# Power_Supply.net
KiCad netlist of a schematic drawn in EAGLE
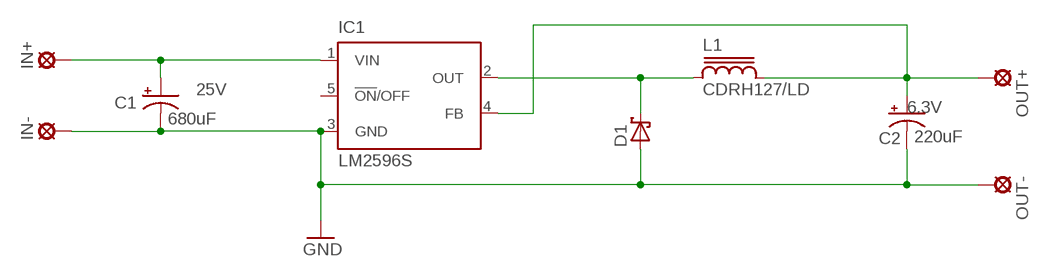
[diagram p0: schematic, sheet 1]

(export (version "E")
  (design (tool "Eeschema 10.0.6"))
  (components
    (comp (ref "C1")
      (value "680uF")
      (footprint "eagle-import:E5-10,5")
      (fields (field (name "VOLTAGE") "25V"))
      (libsource (lib "eagle-import") (part "CPOL-USE5-10.5"))
    )
    (comp (ref "C2")
      (value "220uF")
      (footprint "eagle-import:UD-6,3X5,8_NICHICON")
      (fields (field (name "VOLTAGE") "6.3V"))
      (libsource (lib "eagle-import") (part "CPOL-USUD-6,3X5,8"))
    )
    (comp (ref "D1")
      (value "SCHOTTKY-DIODESMD")
      (footprint "eagle-import:SMB")
      (libsource (lib "eagle-import") (part "SCHOTTKY-DIODESMD"))
    )
    (comp (ref "IC1")
      (value "LM2596S")
      (footprint "eagle-import:TO263-5")
      (fields (field (name "MF") "NATIONAL SEMICONDUCTOR") (field (name "MPN") "LM2596S-ADJ/NOPB"))
      (libsource (lib "eagle-import") (part "LM2596S"))
    )
    (comp (ref "IN+")
      (value "LSP13")
      (footprint "eagle-import:LSP13")
      (libsource (lib "eagle-import") (part "LSP13"))
    )
    (comp (ref "IN-")
      (value "LSP13")
      (footprint "eagle-import:LSP13")
      (libsource (lib "eagle-import") (part "LSP13"))
    )
    (comp (ref "L1")
      (value "CDRH127/LD")
      (footprint "eagle-import:CDRH127_LD")
      (libsource (lib "eagle-import") (part "CDRH127/LD"))
    )
    (comp (ref "OUT+")
      (value "LSP13")
      (footprint "eagle-import:LSP13")
      (libsource (lib "eagle-import") (part "LSP13"))
    )
    (comp (ref "OUT-")
      (value "LSP13")
      (footprint "eagle-import:LSP13")
      (libsource (lib "eagle-import") (part "LSP13"))
    )
  )
  (nets
    (net (code "1") (name "GND") (class "Default")
      (node (ref "C1") (pin "-") (pinfunction "-_-") (pintype "passive"))
      (node (ref "C2") (pin "-") (pinfunction "-_-") (pintype "passive"))
      (node (ref "D1") (pin "A") (pinfunction "A_A") (pintype "passive"))
      (node (ref "IC1") (pin "3") (pinfunction "GND_3") (pintype "power_in"))
      (node (ref "IN-") (pin "MP") (pinfunction "MP_MP") (pintype "passive"))
      (node (ref "OUT-") (pin "MP") (pinfunction "MP_MP") (pintype "passive"))
    )
    (net (code "2") (name "Net-(IC1-FB)") (class "Default")
      (node (ref "C2") (pin "+") (pinfunction "+_+") (pintype "passive"))
      (node (ref "IC1") (pin "4") (pinfunction "FB_4") (pintype "input"))
      (node (ref "L1") (pin "2") (pinfunction "2_2") (pintype "passive"))
      (node (ref "OUT+") (pin "MP") (pinfunction "MP_MP") (pintype "passive"))
    )
    (net (code "3") (name "Net-(IC1-OUT)") (class "Default")
      (node (ref "D1") (pin "C") (pinfunction "C_C") (pintype "passive"))
      (node (ref "IC1") (pin "2") (pinfunction "OUT_2") (pintype "output"))
      (node (ref "L1") (pin "1") (pinfunction "1_1") (pintype "passive"))
    )
    (net (code "4") (name "Net-(IC1-VIN)") (class "Default")
      (node (ref "C1") (pin "+") (pinfunction "+_+") (pintype "passive"))
      (node (ref "IC1") (pin "1") (pinfunction "VIN_1") (pintype "input"))
      (node (ref "IN+") (pin "MP") (pinfunction "MP_MP") (pintype "passive"))
    )
    (net (code "5") (name "unconnected-(IC1-~{ON}{slash}OFF-Pad5)") (class "Default")
      (node (ref "IC1") (pin "5") (pinfunction "~{ON}/OFF_5") (pintype "input"))
    )
  )
)
